# DTMF-FSK.net
KiCad netlist of a schematic drawn in Altium Designer
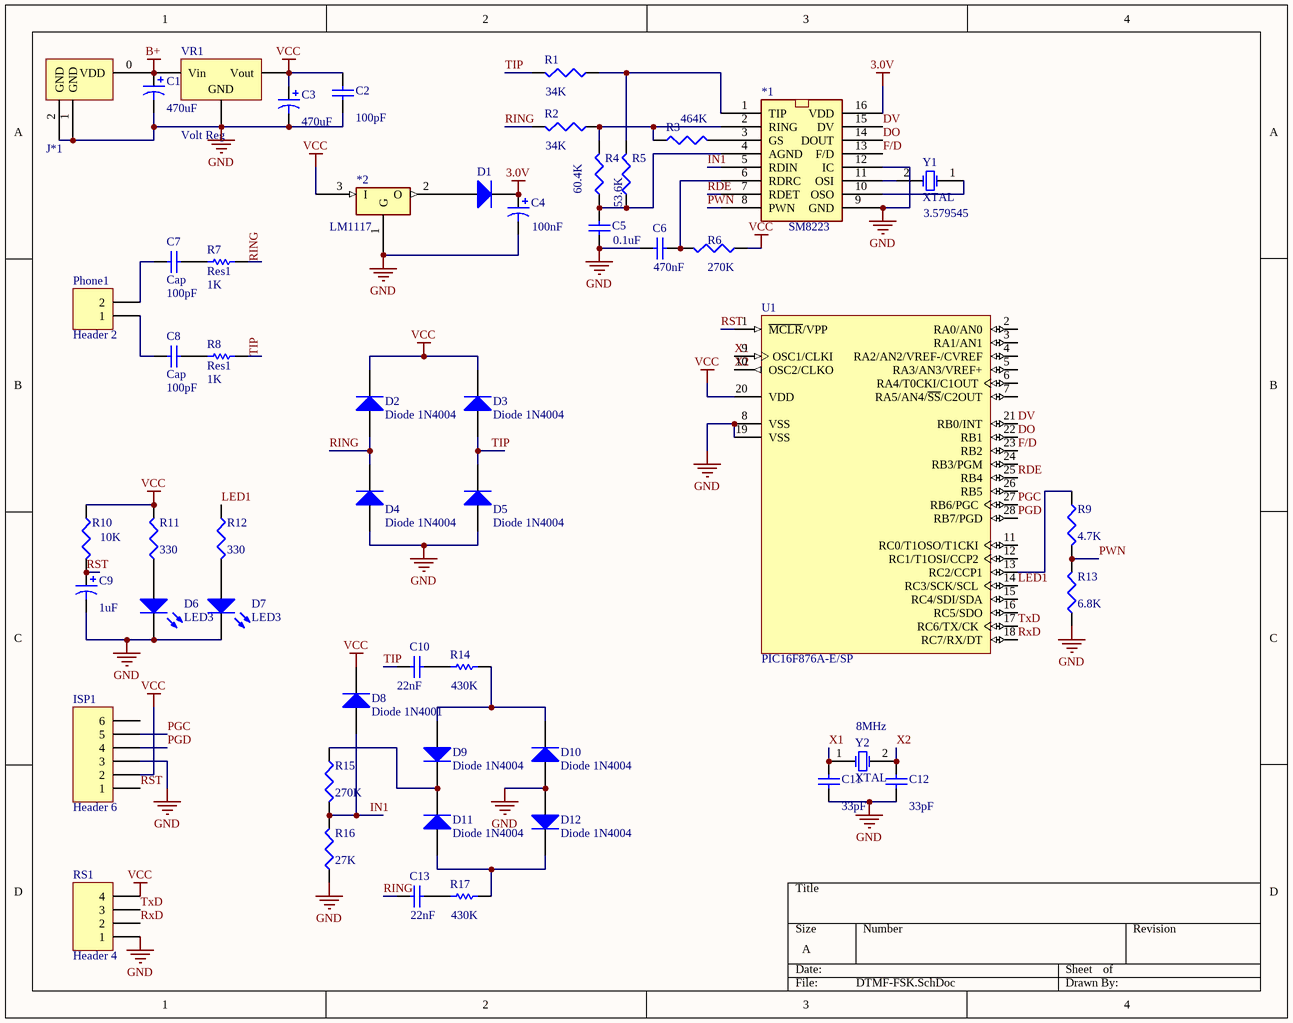
[diagram p0: DTMF-FSK.SchDoc]

(export (version "E")
  (design (tool "Eeschema 10.0.6"))
  (components
    (comp (ref "*1") (value "SM8223") (footprint "NE016") (libsource (lib "MyLibrary") (part "SM8223")))
    (comp (ref "*2") (value "LM1117") (footprint "LM1117") (libsource (lib "MyLibrary") (part "LM1117")))
    (comp (ref "C1")
      (value "470uF")
      (footprint "CAPPR5-5x5")
      (description "Polarized Capacitor (Radial)")
      (fields (field (name "Comment") "Cap Pol1") (field (name "PUBLISHER") "Altium Limited"))
      (libsource (lib "Miscellaneous Devices") (part "Cap Pol1"))
    )
    (comp (ref "C2")
      (value "100pF")
      (footprint "CAPC1608L")
      (description "Capacitor (Semiconductor SIM Model)")
      (fields (field (name "Comment") "Cap Semi") (field (name "PUBLISHER") "Altium Limited"))
      (libsource (lib "Miscellaneous Devices") (part "Cap Semi"))
    )
    (comp (ref "C3")
      (value "470uF")
      (footprint "CAPPR5-5x5")
      (description "Polarized Capacitor (Radial)")
      (fields (field (name "Comment") "Cap Pol1") (field (name "PUBLISHER") "Altium Limited"))
      (libsource (lib "Miscellaneous Devices") (part "Cap Pol1"))
    )
    (comp (ref "C4")
      (value "100nF")
      (footprint "CAPC4532L")
      (description "Polarized Capacitor (Surface Mount)")
      (fields (field (name "Comment") "Cap Pol3") (field (name "PUBLISHER") "Altium Limited"))
      (libsource (lib "Miscellaneous Devices") (part "Cap Pol3"))
    )
    (comp (ref "C5")
      (value "0.1uF")
      (footprint "CAPC1608L")
      (description "Capacitor (Semiconductor SIM Model)")
      (fields (field (name "Comment") "Cap Semi") (field (name "PUBLISHER") "Altium Limited"))
      (libsource (lib "Miscellaneous Devices") (part "Cap Semi"))
    )
    (comp (ref "C6")
      (value "470nF")
      (footprint "CAPC3216L")
      (description "Capacitor (Semiconductor SIM Model)")
      (fields (field (name "Comment") "Cap Semi") (field (name "PUBLISHER") "Altium Limited"))
      (libsource (lib "Miscellaneous Devices") (part "Cap Semi"))
    )
    (comp (ref "C7")
      (value "Cap")
      (footprint "CAPR2.54-5.1x3.2")
      (description "Capacitor")
      (fields (field (name "ALTIUM_VALUE") "100pF") (field (name "PUBLISHER") "Altium Limited"))
      (libsource (lib "Miscellaneous Devices") (part "Cap"))
    )
    (comp (ref "C8")
      (value "Cap")
      (footprint "CAPR2.54-5.1x3.2")
      (description "Capacitor")
      (fields (field (name "ALTIUM_VALUE") "100pF") (field (name "PUBLISHER") "Altium Limited"))
      (libsource (lib "Miscellaneous Devices") (part "Cap"))
    )
    (comp (ref "C9")
      (value "1uF")
      (footprint "CAPC1608L")
      (description "Polarized Capacitor (Radial)")
      (fields (field (name "Comment") "Cap Pol1") (field (name "PUBLISHER") "Altium Limited"))
      (libsource (lib "Miscellaneous Devices") (part "Cap Pol1"))
    )
    (comp (ref "C10")
      (value "22nF")
      (footprint "CAPR2.54-5.1x3.2")
      (description "Capacitor")
      (fields (field (name "Comment") "Cap") (field (name "PUBLISHER") "Altium Limited"))
      (libsource (lib "Miscellaneous Devices") (part "Cap"))
    )
    (comp (ref "C11")
      (value "33pF")
      (footprint "CAPC1608L")
      (description "Capacitor (Semiconductor SIM Model)")
      (fields (field (name "Comment") "Cap Semi") (field (name "PUBLISHER") "Altium Limited"))
      (libsource (lib "Miscellaneous Devices") (part "Cap Semi"))
    )
    (comp (ref "C12")
      (value "33pF")
      (footprint "CAPC1608L")
      (description "Capacitor (Semiconductor SIM Model)")
      (fields (field (name "Comment") "Cap Semi") (field (name "PUBLISHER") "Altium Limited"))
      (libsource (lib "Miscellaneous Devices") (part "Cap Semi"))
    )
    (comp (ref "C13")
      (value "22nF")
      (footprint "CAPR2.54-5.1x3.2")
      (description "Capacitor")
      (fields (field (name "Comment") "Cap") (field (name "PUBLISHER") "Altium Limited"))
      (libsource (lib "Miscellaneous Devices") (part "Cap"))
    )
    (comp (ref "D1")
      (value "Diode")
      (footprint "DSO-C2/X3.3")
      (description "Default Diode")
      (fields (field (name "PUBLISHER") "Altium Limited"))
      (libsource (lib "Miscellaneous Devices") (part "Diode"))
    )
    (comp (ref "D2")
      (value "Diode 1N4004")
      (footprint "DIO10.46-5.3x2.8")
      (description "1 Amp General Purpose Rectifier")
      (fields (field (name "PUBLISHER") "Altium Limited"))
      (libsource (lib "Miscellaneous Devices") (part "Diode 1N4004"))
    )
    (comp (ref "D3")
      (value "Diode 1N4004")
      (footprint "DIO10.46-5.3x2.8")
      (description "1 Amp General Purpose Rectifier")
      (fields (field (name "PUBLISHER") "Altium Limited"))
      (libsource (lib "Miscellaneous Devices") (part "Diode 1N4004"))
    )
    (comp (ref "D4")
      (value "Diode 1N4004")
      (footprint "DIO10.46-5.3x2.8")
      (description "1 Amp General Purpose Rectifier")
      (fields (field (name "PUBLISHER") "Altium Limited"))
      (libsource (lib "Miscellaneous Devices") (part "Diode 1N4004"))
    )
    (comp (ref "D5")
      (value "Diode 1N4004")
      (footprint "DIO10.46-5.3x2.8")
      (description "1 Amp General Purpose Rectifier")
      (fields (field (name "PUBLISHER") "Altium Limited"))
      (libsource (lib "Miscellaneous Devices") (part "Diode 1N4004"))
    )
    (comp (ref "D6")
      (value "LED3")
      (footprint "DSO-C2/D5.6")
      (description "Typical BLUE SiC LED")
      (fields (field (name "PUBLISHER") "Altium Limited"))
      (libsource (lib "Miscellaneous Devices") (part "LED3"))
    )
    (comp (ref "D7")
      (value "LED3")
      (footprint "DSO-C2/D5.6")
      (description "Typical BLUE SiC LED")
      (fields (field (name "PUBLISHER") "Altium Limited"))
      (libsource (lib "Miscellaneous Devices") (part "LED3"))
    )
    (comp (ref "D8")
      (value "Diode 1N4001")
      (footprint "DIO10.46-5.3x2.8")
      (description "1 Amp General Purpose Rectifier")
      (fields (field (name "PUBLISHER") "Altium Limited"))
      (libsource (lib "Miscellaneous Devices") (part "Diode 1N4001"))
    )
    (comp (ref "D9")
      (value "Diode 1N4004")
      (footprint "DIO10.46-5.3x2.8")
      (description "1 Amp General Purpose Rectifier")
      (fields (field (name "PUBLISHER") "Altium Limited"))
      (libsource (lib "Miscellaneous Devices") (part "Diode 1N4004"))
    )
    (comp (ref "D10")
      (value "Diode 1N4004")
      (footprint "DIO10.46-5.3x2.8")
      (description "1 Amp General Purpose Rectifier")
      (fields (field (name "PUBLISHER") "Altium Limited"))
      (libsource (lib "Miscellaneous Devices") (part "Diode 1N4004"))
    )
    (comp (ref "D11")
      (value "Diode 1N4004")
      (footprint "DIO10.46-5.3x2.8")
      (description "1 Amp General Purpose Rectifier")
      (fields (field (name "PUBLISHER") "Altium Limited"))
      (libsource (lib "Miscellaneous Devices") (part "Diode 1N4004"))
    )
    (comp (ref "D12")
      (value "Diode 1N4004")
      (footprint "DIO10.46-5.3x2.8")
      (description "1 Amp General Purpose Rectifier")
      (fields (field (name "PUBLISHER") "Altium Limited"))
      (libsource (lib "Miscellaneous Devices") (part "Diode 1N4004"))
    )
    (comp (ref "ISP1")
      (value "Header 6")
      (footprint "HDR1X6")
      (description "Header, 6-Pin")
      (fields (field (name "PUBLISHER") "Altium Limited"))
      (libsource (lib "Miscellaneous Connectors") (part "Header 6"))
    )
    (comp (ref "J*1") (value "Jac_DC") (footprint "Jac_DC") (libsource (lib "MyLibrary") (part "Jac_DC")))
    (comp (ref "Phone1")
      (value "Header 2")
      (footprint "HDR1X2")
      (description "Header, 2-Pin")
      (fields (field (name "PUBLISHER") "Altium Limited"))
      (libsource (lib "Miscellaneous Connectors") (part "Header 2"))
    )
    (comp (ref "R1")
      (value "34K")
      (footprint "RESC1608L")
      (description "Resistor")
      (fields (field (name "Comment") "Res3") (field (name "PUBLISHER") "Altium Limited"))
      (libsource (lib "Miscellaneous Devices") (part "Res3"))
    )
    (comp (ref "R2")
      (value "34K")
      (footprint "RESC1608L")
      (description "Resistor")
      (fields (field (name "Comment") "Res3") (field (name "PUBLISHER") "Altium Limited"))
      (libsource (lib "Miscellaneous Devices") (part "Res3"))
    )
    (comp (ref "R3")
      (value "464K")
      (footprint "RESC1608L")
      (description "Resistor")
      (fields (field (name "Comment") "Res3") (field (name "PUBLISHER") "Altium Limited"))
      (libsource (lib "Miscellaneous Devices") (part "Res3"))
    )
    (comp (ref "R4")
      (value "60.4K")
      (footprint "RESC1608L")
      (description "Resistor")
      (fields (field (name "Comment") "Res3") (field (name "PUBLISHER") "Altium Limited"))
      (libsource (lib "Miscellaneous Devices") (part "Res3"))
    )
    (comp (ref "R5")
      (value "53.6K")
      (footprint "RESC1608L")
      (description "Resistor")
      (fields (field (name "Comment") "Res3") (field (name "PUBLISHER") "Altium Limited"))
      (libsource (lib "Miscellaneous Devices") (part "Res3"))
    )
    (comp (ref "R6")
      (value "270K")
      (footprint "RESC1608L")
      (description "Resistor")
      (fields (field (name "Comment") "Res3") (field (name "PUBLISHER") "Altium Limited"))
      (libsource (lib "Miscellaneous Devices") (part "Res3"))
    )
    (comp (ref "R7")
      (value "Res1")
      (footprint "AXIAL-0.3")
      (description "Resistor")
      (fields (field (name "ALTIUM_VALUE") "1K") (field (name "PUBLISHER") "Altium Limited"))
      (libsource (lib "Miscellaneous Devices") (part "Res1"))
    )
    (comp (ref "R8")
      (value "Res1")
      (footprint "AXIAL-0.3")
      (description "Resistor")
      (fields (field (name "ALTIUM_VALUE") "1K") (field (name "PUBLISHER") "Altium Limited"))
      (libsource (lib "Miscellaneous Devices") (part "Res1"))
    )
    (comp (ref "R9")
      (value "4.7K")
      (footprint "RESC1608L")
      (description "Resistor")
      (fields (field (name "Comment") "Res3") (field (name "PUBLISHER") "Altium Limited"))
      (libsource (lib "Miscellaneous Devices") (part "Res3"))
    )
    (comp (ref "R10")
      (value "10K")
      (footprint "RESC1608L")
      (description "Resistor")
      (fields (field (name "Comment") "Res3") (field (name "PUBLISHER") "Altium Limited"))
      (libsource (lib "Miscellaneous Devices") (part "Res3"))
    )
    (comp (ref "R11")
      (value "330")
      (footprint "RESC1608L")
      (description "Resistor")
      (fields (field (name "Comment") "Res3") (field (name "PUBLISHER") "Altium Limited"))
      (libsource (lib "Miscellaneous Devices") (part "Res3"))
    )
    (comp (ref "R12")
      (value "330")
      (footprint "RESC1608L")
      (description "Resistor")
      (fields (field (name "Comment") "Res3") (field (name "PUBLISHER") "Altium Limited"))
      (libsource (lib "Miscellaneous Devices") (part "Res3"))
    )
    (comp (ref "R13")
      (value "6.8K")
      (footprint "RESC1608L")
      (description "Resistor")
      (fields (field (name "Comment") "Res3") (field (name "PUBLISHER") "Altium Limited"))
      (libsource (lib "Miscellaneous Devices") (part "Res3"))
    )
    (comp (ref "R14")
      (value "430K")
      (footprint "AXIAL-0.3")
      (description "Resistor")
      (fields (field (name "Comment") "Res1") (field (name "PUBLISHER") "Altium Limited"))
      (libsource (lib "Miscellaneous Devices") (part "Res1"))
    )
    (comp (ref "R15")
      (value "270K")
      (footprint "RESC1608L")
      (description "Resistor")
      (fields (field (name "Comment") "Res3") (field (name "PUBLISHER") "Altium Limited"))
      (libsource (lib "Miscellaneous Devices") (part "Res3"))
    )
    (comp (ref "R16")
      (value "27K")
      (footprint "RESC1608L")
      (description "Resistor")
      (fields (field (name "Comment") "Res3") (field (name "PUBLISHER") "Altium Limited"))
      (libsource (lib "Miscellaneous Devices") (part "Res3"))
    )
    (comp (ref "R17")
      (value "430K")
      (footprint "AXIAL-0.3")
      (description "Resistor")
      (fields (field (name "Comment") "Res1") (field (name "PUBLISHER") "Altium Limited"))
      (libsource (lib "Miscellaneous Devices") (part "Res1"))
    )
    (comp (ref "RS1")
      (value "Header 4")
      (footprint "HDR1X4")
      (description "Header, 4-Pin")
      (fields (field (name "PUBLISHER") "Altium Limited"))
      (libsource (lib "Miscellaneous Connectors") (part "Header 4"))
    )
    (comp (ref "U1")
      (value "PIC16F876A-E/SP")
      (footprint "SPDIP300-SP28")
      (fields (field (name "PUBLISHER") "Altium Limited"))
      (libsource (lib "Microchip Microcontroller 8-Bit PIC16") (part "PIC16F876A-E/SP"))
    )
    (comp (ref "VR1")
      (value "Volt Reg")
      (footprint "TO-220")
      (description "Voltage Regulator")
      (fields (field (name "PUBLISHER") "Altium Limited"))
      (libsource (lib "Miscellaneous Devices") (part "Volt Reg"))
    )
    (comp (ref "Y1")
      (value "XTAL")
      (footprint "BCY-W2/D3.1")
      (description "Crystal Oscillator")
      (fields (field (name "ALTIUM_UNNAMED_1") "3.579545") (field (name "PUBLISHER") "Altium Limited"))
      (libsource (lib "Miscellaneous Devices") (part "XTAL"))
    )
    (comp (ref "Y2")
      (value "XTAL")
      (footprint "Miscellaneous Devices:CAPR5-4X5")
      (description "Crystal Oscillator")
      (fields (field (name "ALTIUM_UNNAMED_1") "8MHz") (field (name "PUBLISHER") "Altium Limited"))
      (libsource (lib "Miscellaneous Devices") (part "XTAL"))
    )
  )
  (nets
    (net (code "1") (name "/DO") (class "Default")
      (node (ref "*1") (pin "14") (pinfunction "DOUT_14") (pintype "passive"))
      (node (ref "U1") (pin "22") (pinfunction "RB1_22") (pintype "bidirectional"))
    )
    (net (code "2") (name "/DV") (class "Default")
      (node (ref "*1") (pin "15") (pinfunction "DV_15") (pintype "passive"))
      (node (ref "U1") (pin "21") (pinfunction "RB0/INT_21") (pintype "bidirectional"))
    )
    (net (code "3") (name "/F{slash}D") (class "Default")
      (node (ref "*1") (pin "13") (pinfunction "F/D_13") (pintype "passive"))
      (node (ref "U1") (pin "23") (pinfunction "RB2_23") (pintype "bidirectional"))
    )
    (net (code "4") (name "/IN1") (class "Default")
      (node (ref "*1") (pin "5") (pinfunction "RDIN_5") (pintype "passive"))
      (node (ref "D8") (pin "1") (pinfunction "A_1") (pintype "passive"))
      (node (ref "R15") (pin "2") (pinfunction "2_2") (pintype "passive"))
      (node (ref "R16") (pin "2") (pinfunction "2_2") (pintype "passive"))
    )
    (net (code "5") (name "/LED1") (class "Default")
      (node (ref "R12") (pin "1") (pinfunction "1_1") (pintype "passive"))
      (node (ref "U1") (pin "14") (pinfunction "RC3/SCK/SCL_14") (pintype "bidirectional"))
    )
    (net (code "6") (name "/PGC") (class "Default")
      (node (ref "ISP1") (pin "5") (pinfunction "5_5") (pintype "passive"))
      (node (ref "U1") (pin "27") (pinfunction "RB6/PGC_27") (pintype "bidirectional"))
    )
    (net (code "7") (name "/PGD") (class "Default")
      (node (ref "ISP1") (pin "4") (pinfunction "4_4") (pintype "passive"))
      (node (ref "U1") (pin "28") (pinfunction "RB7/PGD_28") (pintype "bidirectional"))
    )
    (net (code "8") (name "/PWN") (class "Default")
      (node (ref "*1") (pin "8") (pinfunction "PWN_8") (pintype "passive"))
      (node (ref "R13") (pin "2") (pinfunction "2_2") (pintype "passive"))
      (node (ref "R9") (pin "2") (pinfunction "2_2") (pintype "passive"))
    )
    (net (code "9") (name "/RDE") (class "Default")
      (node (ref "*1") (pin "7") (pinfunction "RDET_7") (pintype "passive"))
      (node (ref "U1") (pin "25") (pinfunction "RB4_25") (pintype "bidirectional"))
    )
    (net (code "10") (name "/RING") (class "Default")
      (node (ref "C13") (pin "1") (pinfunction "1_1") (pintype "passive"))
      (node (ref "D2") (pin "1") (pinfunction "A_1") (pintype "passive"))
      (node (ref "D4") (pin "2") (pinfunction "K_2") (pintype "passive"))
      (node (ref "R2") (pin "2") (pinfunction "2_2") (pintype "passive"))
      (node (ref "R7") (pin "1") (pinfunction "1_1") (pintype "passive"))
    )
    (net (code "11") (name "/RST") (class "Default")
      (node (ref "C9") (pin "1") (pinfunction "1_1") (pintype "passive"))
      (node (ref "ISP1") (pin "1") (pinfunction "1_1") (pintype "passive"))
      (node (ref "R10") (pin "2") (pinfunction "2_2") (pintype "passive"))
      (node (ref "U1") (pin "1") (pinfunction "~{MCLR}/VPP_1") (pintype "input"))
    )
    (net (code "12") (name "/RxD") (class "Default")
      (node (ref "RS1") (pin "2") (pinfunction "2_2") (pintype "passive"))
      (node (ref "U1") (pin "18") (pinfunction "RC7/RX/DT_18") (pintype "bidirectional"))
    )
    (net (code "13") (name "/TIP") (class "Default")
      (node (ref "C10") (pin "1") (pinfunction "1_1") (pintype "passive"))
      (node (ref "D3") (pin "1") (pinfunction "A_1") (pintype "passive"))
      (node (ref "D5") (pin "2") (pinfunction "K_2") (pintype "passive"))
      (node (ref "R1") (pin "2") (pinfunction "2_2") (pintype "passive"))
      (node (ref "R8") (pin "1") (pinfunction "1_1") (pintype "passive"))
    )
    (net (code "14") (name "/TxD") (class "Default")
      (node (ref "RS1") (pin "3") (pinfunction "3_3") (pintype "passive"))
      (node (ref "U1") (pin "17") (pinfunction "RC6/TX/CK_17") (pintype "bidirectional"))
    )
    (net (code "15") (name "/X1") (class "Default")
      (node (ref "C11") (pin "1") (pinfunction "1_1") (pintype "passive"))
      (node (ref "U1") (pin "9") (pinfunction "OSC1/CLKI_9") (pintype "input"))
      (node (ref "Y2") (pin "1") (pinfunction "OSC1_1") (pintype "passive"))
    )
    (net (code "16") (name "/X2") (class "Default")
      (node (ref "C12") (pin "1") (pinfunction "1_1") (pintype "passive"))
      (node (ref "U1") (pin "10") (pinfunction "OSC2/CLKO_10") (pintype "output"))
      (node (ref "Y2") (pin "2") (pinfunction "OSC2_2") (pintype "passive"))
    )
    (net (code "17") (name "3.0V") (class "Default")
      (node (ref "*1") (pin "16") (pinfunction "VDD_16") (pintype "passive"))
      (node (ref "C4") (pin "1") (pinfunction "1_1") (pintype "passive"))
      (node (ref "D1") (pin "2") (pinfunction "K_2") (pintype "passive"))
    )
    (net (code "18") (name "B+") (class "Default")
      (node (ref "C1") (pin "1") (pinfunction "1_1") (pintype "passive"))
      (node (ref "J*1") (pin "0") (pinfunction "VDD_0") (pintype "power_in"))
      (node (ref "VR1") (pin "1") (pinfunction "Vin_1") (pintype "passive"))
    )
    (net (code "19") (name "GND") (class "Default")
      (node (ref "*1") (pin "12") (pinfunction "IC_12") (pintype "passive"))
      (node (ref "*1") (pin "9") (pinfunction "GND_9") (pintype "passive"))
      (node (ref "*2") (pin "1") (pinfunction "G_1") (pintype "power_in"))
      (node (ref "C1") (pin "2") (pinfunction "2_2") (pintype "passive"))
      (node (ref "C11") (pin "2") (pinfunction "2_2") (pintype "passive"))
      (node (ref "C12") (pin "2") (pinfunction "2_2") (pintype "passive"))
      (node (ref "C2") (pin "1") (pinfunction "1_1") (pintype "passive"))
      (node (ref "C3") (pin "2") (pinfunction "2_2") (pintype "passive"))
      (node (ref "C4") (pin "2") (pinfunction "2_2") (pintype "passive"))
      (node (ref "C5") (pin "1") (pinfunction "1_1") (pintype "passive"))
      (node (ref "C6") (pin "1") (pinfunction "1_1") (pintype "passive"))
      (node (ref "C9") (pin "2") (pinfunction "2_2") (pintype "passive"))
      (node (ref "D10") (pin "1") (pinfunction "A_1") (pintype "passive"))
      (node (ref "D12") (pin "1") (pinfunction "A_1") (pintype "passive"))
      (node (ref "D4") (pin "1") (pinfunction "A_1") (pintype "passive"))
      (node (ref "D5") (pin "1") (pinfunction "A_1") (pintype "passive"))
      (node (ref "D6") (pin "2") (pinfunction "K_2") (pintype "passive"))
      (node (ref "D7") (pin "2") (pinfunction "K_2") (pintype "passive"))
      (node (ref "ISP1") (pin "3") (pinfunction "3_3") (pintype "passive"))
      (node (ref "J*1") (pin "1") (pinfunction "GND_1") (pintype "power_in"))
      (node (ref "J*1") (pin "2") (pinfunction "GND_2") (pintype "power_in"))
      (node (ref "R13") (pin "1") (pinfunction "1_1") (pintype "passive"))
      (node (ref "R16") (pin "1") (pinfunction "1_1") (pintype "passive"))
      (node (ref "RS1") (pin "1") (pinfunction "1_1") (pintype "passive"))
      (node (ref "U1") (pin "19") (pinfunction "VSS_19") (pintype "power_in"))
      (node (ref "U1") (pin "8") (pinfunction "VSS_8") (pintype "power_in"))
      (node (ref "VR1") (pin "2") (pinfunction "GND_2") (pintype "passive"))
    )
    (net (code "20") (name "Net-(*1-AGND)") (class "Default")
      (node (ref "*1") (pin "4") (pinfunction "AGND_4") (pintype "passive"))
      (node (ref "C5") (pin "2") (pinfunction "2_2") (pintype "passive"))
      (node (ref "R4") (pin "1") (pinfunction "1_1") (pintype "passive"))
      (node (ref "R5") (pin "1") (pinfunction "1_1") (pintype "passive"))
    )
    (net (code "21") (name "Net-(*1-GS)") (class "Default")
      (node (ref "*1") (pin "3") (pinfunction "GS_3") (pintype "passive"))
      (node (ref "R3") (pin "2") (pinfunction "2_2") (pintype "passive"))
    )
    (net (code "22") (name "Net-(*1-OSI)") (class "Default")
      (node (ref "*1") (pin "11") (pinfunction "OSI_11") (pintype "passive"))
      (node (ref "Y1") (pin "2") (pinfunction "OSC2_2") (pintype "passive"))
    )
    (net (code "23") (name "Net-(*1-OSO)") (class "Default")
      (node (ref "*1") (pin "10") (pinfunction "OSO_10") (pintype "passive"))
      (node (ref "Y1") (pin "1") (pinfunction "OSC1_1") (pintype "passive"))
    )
    (net (code "24") (name "Net-(*1-RDRC)") (class "Default")
      (node (ref "*1") (pin "6") (pinfunction "RDRC_6") (pintype "passive"))
      (node (ref "C6") (pin "2") (pinfunction "2_2") (pintype "passive"))
      (node (ref "R6") (pin "2") (pinfunction "2_2") (pintype "passive"))
    )
    (net (code "25") (name "Net-(*1-RING)") (class "Default")
      (node (ref "*1") (pin "2") (pinfunction "RING_2") (pintype "passive"))
      (node (ref "R2") (pin "1") (pinfunction "1_1") (pintype "passive"))
      (node (ref "R3") (pin "1") (pinfunction "1_1") (pintype "passive"))
      (node (ref "R4") (pin "2") (pinfunction "2_2") (pintype "passive"))
    )
    (net (code "26") (name "Net-(*1-TIP)") (class "Default")
      (node (ref "*1") (pin "1") (pinfunction "TIP_1") (pintype "passive"))
      (node (ref "R1") (pin "1") (pinfunction "1_1") (pintype "passive"))
      (node (ref "R5") (pin "2") (pinfunction "2_2") (pintype "passive"))
    )
    (net (code "27") (name "Net-(*2-O)") (class "Default")
      (node (ref "*2") (pin "2") (pinfunction "O_2") (pintype "output"))
      (node (ref "D1") (pin "1") (pinfunction "A_1") (pintype "passive"))
    )
    (net (code "28") (name "Net-(C7-Pad1)") (class "Default")
      (node (ref "C7") (pin "1") (pinfunction "1_1") (pintype "passive"))
      (node (ref "R7") (pin "2") (pinfunction "2_2") (pintype "passive"))
    )
    (net (code "29") (name "Net-(C7-Pad2)") (class "Default")
      (node (ref "C7") (pin "2") (pinfunction "2_2") (pintype "passive"))
      (node (ref "Phone1") (pin "2") (pinfunction "2_2") (pintype "passive"))
    )
    (net (code "30") (name "Net-(C8-Pad1)") (class "Default")
      (node (ref "C8") (pin "1") (pinfunction "1_1") (pintype "passive"))
      (node (ref "R8") (pin "2") (pinfunction "2_2") (pintype "passive"))
    )
    (net (code "31") (name "Net-(C8-Pad2)") (class "Default")
      (node (ref "C8") (pin "2") (pinfunction "2_2") (pintype "passive"))
      (node (ref "Phone1") (pin "1") (pinfunction "1_1") (pintype "passive"))
    )
    (net (code "32") (name "Net-(C10-Pad2)") (class "Default")
      (node (ref "C10") (pin "2") (pinfunction "2_2") (pintype "passive"))
      (node (ref "R14") (pin "2") (pinfunction "2_2") (pintype "passive"))
    )
    (net (code "33") (name "Net-(C13-Pad2)") (class "Default")
      (node (ref "C13") (pin "2") (pinfunction "2_2") (pintype "passive"))
      (node (ref "R17") (pin "2") (pinfunction "2_2") (pintype "passive"))
    )
    (net (code "34") (name "Net-(D6-A)") (class "Default")
      (node (ref "D6") (pin "1") (pinfunction "A_1") (pintype "passive"))
      (node (ref "R11") (pin "1") (pinfunction "1_1") (pintype "passive"))
    )
    (net (code "35") (name "Net-(D7-A)") (class "Default")
      (node (ref "D7") (pin "1") (pinfunction "A_1") (pintype "passive"))
      (node (ref "R12") (pin "2") (pinfunction "2_2") (pintype "passive"))
    )
    (net (code "36") (name "Net-(D10-K)") (class "Default")
      (node (ref "D10") (pin "2") (pinfunction "K_2") (pintype "passive"))
      (node (ref "D9") (pin "1") (pinfunction "A_1") (pintype "passive"))
      (node (ref "R14") (pin "1") (pinfunction "1_1") (pintype "passive"))
    )
    (net (code "37") (name "Net-(D11-A)") (class "Default")
      (node (ref "D11") (pin "1") (pinfunction "A_1") (pintype "passive"))
      (node (ref "D12") (pin "2") (pinfunction "K_2") (pintype "passive"))
      (node (ref "R17") (pin "1") (pinfunction "1_1") (pintype "passive"))
    )
    (net (code "38") (name "Net-(D11-K)") (class "Default")
      (node (ref "D11") (pin "2") (pinfunction "K_2") (pintype "passive"))
      (node (ref "D9") (pin "2") (pinfunction "K_2") (pintype "passive"))
      (node (ref "R15") (pin "1") (pinfunction "1_1") (pintype "passive"))
    )
    (net (code "39") (name "Net-(U1-RC2{slash}CCP1)") (class "Default")
      (node (ref "R9") (pin "1") (pinfunction "1_1") (pintype "passive"))
      (node (ref "U1") (pin "13") (pinfunction "RC2/CCP1_13") (pintype "bidirectional"))
    )
    (net (code "40") (name "VCC") (class "Default")
      (node (ref "*2") (pin "3") (pinfunction "I_3") (pintype "input"))
      (node (ref "C2") (pin "2") (pinfunction "2_2") (pintype "passive"))
      (node (ref "C3") (pin "1") (pinfunction "1_1") (pintype "passive"))
      (node (ref "D2") (pin "2") (pinfunction "K_2") (pintype "passive"))
      (node (ref "D3") (pin "2") (pinfunction "K_2") (pintype "passive"))
      (node (ref "D8") (pin "2") (pinfunction "K_2") (pintype "passive"))
      (node (ref "ISP1") (pin "2") (pinfunction "2_2") (pintype "passive"))
      (node (ref "R10") (pin "1") (pinfunction "1_1") (pintype "passive"))
      (node (ref "R11") (pin "2") (pinfunction "2_2") (pintype "passive"))
      (node (ref "R6") (pin "1") (pinfunction "1_1") (pintype "passive"))
      (node (ref "RS1") (pin "4") (pinfunction "4_4") (pintype "passive"))
      (node (ref "U1") (pin "20") (pinfunction "VDD_20") (pintype "power_in"))
      (node (ref "VR1") (pin "3") (pinfunction "Vout_3") (pintype "passive"))
    )
    (net (code "41") (name "unconnected-(ISP1-Pad6)") (class "Default")
      (node (ref "ISP1") (pin "6") (pinfunction "6_6") (pintype "passive"))
    )
    (net (code "42") (name "unconnected-(U1-RA0{slash}AN0-Pad2)") (class "Default")
      (node (ref "U1") (pin "2") (pinfunction "RA0/AN0_2") (pintype "bidirectional"))
    )
    (net (code "43") (name "unconnected-(U1-RA1{slash}AN1-Pad3)") (class "Default")
      (node (ref "U1") (pin "3") (pinfunction "RA1/AN1_3") (pintype "bidirectional"))
    )
    (net (code "44") (name "unconnected-(U1-RA2{slash}AN2{slash}VREF-{slash}CVREF-Pad4)") (class "Default")
      (node (ref "U1") (pin "4") (pinfunction "RA2/AN2/VREF-/CVREF_4") (pintype "bidirectional"))
    )
    (net (code "45") (name "unconnected-(U1-RA3{slash}AN3{slash}VREF+-Pad5)") (class "Default")
      (node (ref "U1") (pin "5") (pinfunction "RA3/AN3/VREF+_5") (pintype "bidirectional"))
    )
    (net (code "46") (name "unconnected-(U1-RA4{slash}T0CKI{slash}C1OUT-Pad6)") (class "Default")
      (node (ref "U1") (pin "6") (pinfunction "RA4/T0CKI/C1OUT_6") (pintype "bidirectional"))
    )
    (net (code "47") (name "unconnected-(U1-RA5{slash}AN4{slash}~{SS}{slash}C2OUT-Pad7)") (class "Default")
      (node (ref "U1") (pin "7") (pinfunction "RA5/AN4/~{SS}/C2OUT_7") (pintype "bidirectional"))
    )
    (net (code "48") (name "unconnected-(U1-RB3{slash}PGM-Pad24)") (class "Default")
      (node (ref "U1") (pin "24") (pinfunction "RB3/PGM_24") (pintype "bidirectional"))
    )
    (net (code "49") (name "unconnected-(U1-RB5-Pad26)") (class "Default")
      (node (ref "U1") (pin "26") (pinfunction "RB5_26") (pintype "bidirectional"))
    )
    (net (code "50") (name "unconnected-(U1-RC0{slash}T1OSO{slash}T1CKI-Pad11)") (class "Default")
      (node (ref "U1") (pin "11") (pinfunction "RC0/T1OSO/T1CKI_11") (pintype "bidirectional"))
    )
    (net (code "51") (name "unconnected-(U1-RC1{slash}T1OSI{slash}CCP2-Pad12)") (class "Default")
      (node (ref "U1") (pin "12") (pinfunction "RC1/T1OSI/CCP2_12") (pintype "bidirectional"))
    )
    (net (code "52") (name "unconnected-(U1-RC4{slash}SDI{slash}SDA-Pad15)") (class "Default")
      (node (ref "U1") (pin "15") (pinfunction "RC4/SDI/SDA_15") (pintype "bidirectional"))
    )
    (net (code "53") (name "unconnected-(U1-RC5{slash}SDO-Pad16)") (class "Default")
      (node (ref "U1") (pin "16") (pinfunction "RC5/SDO_16") (pintype "bidirectional"))
    )
  )
)
